# arduino-doorbell.net
KiCad netlist of a schematic drawn in EAGLE
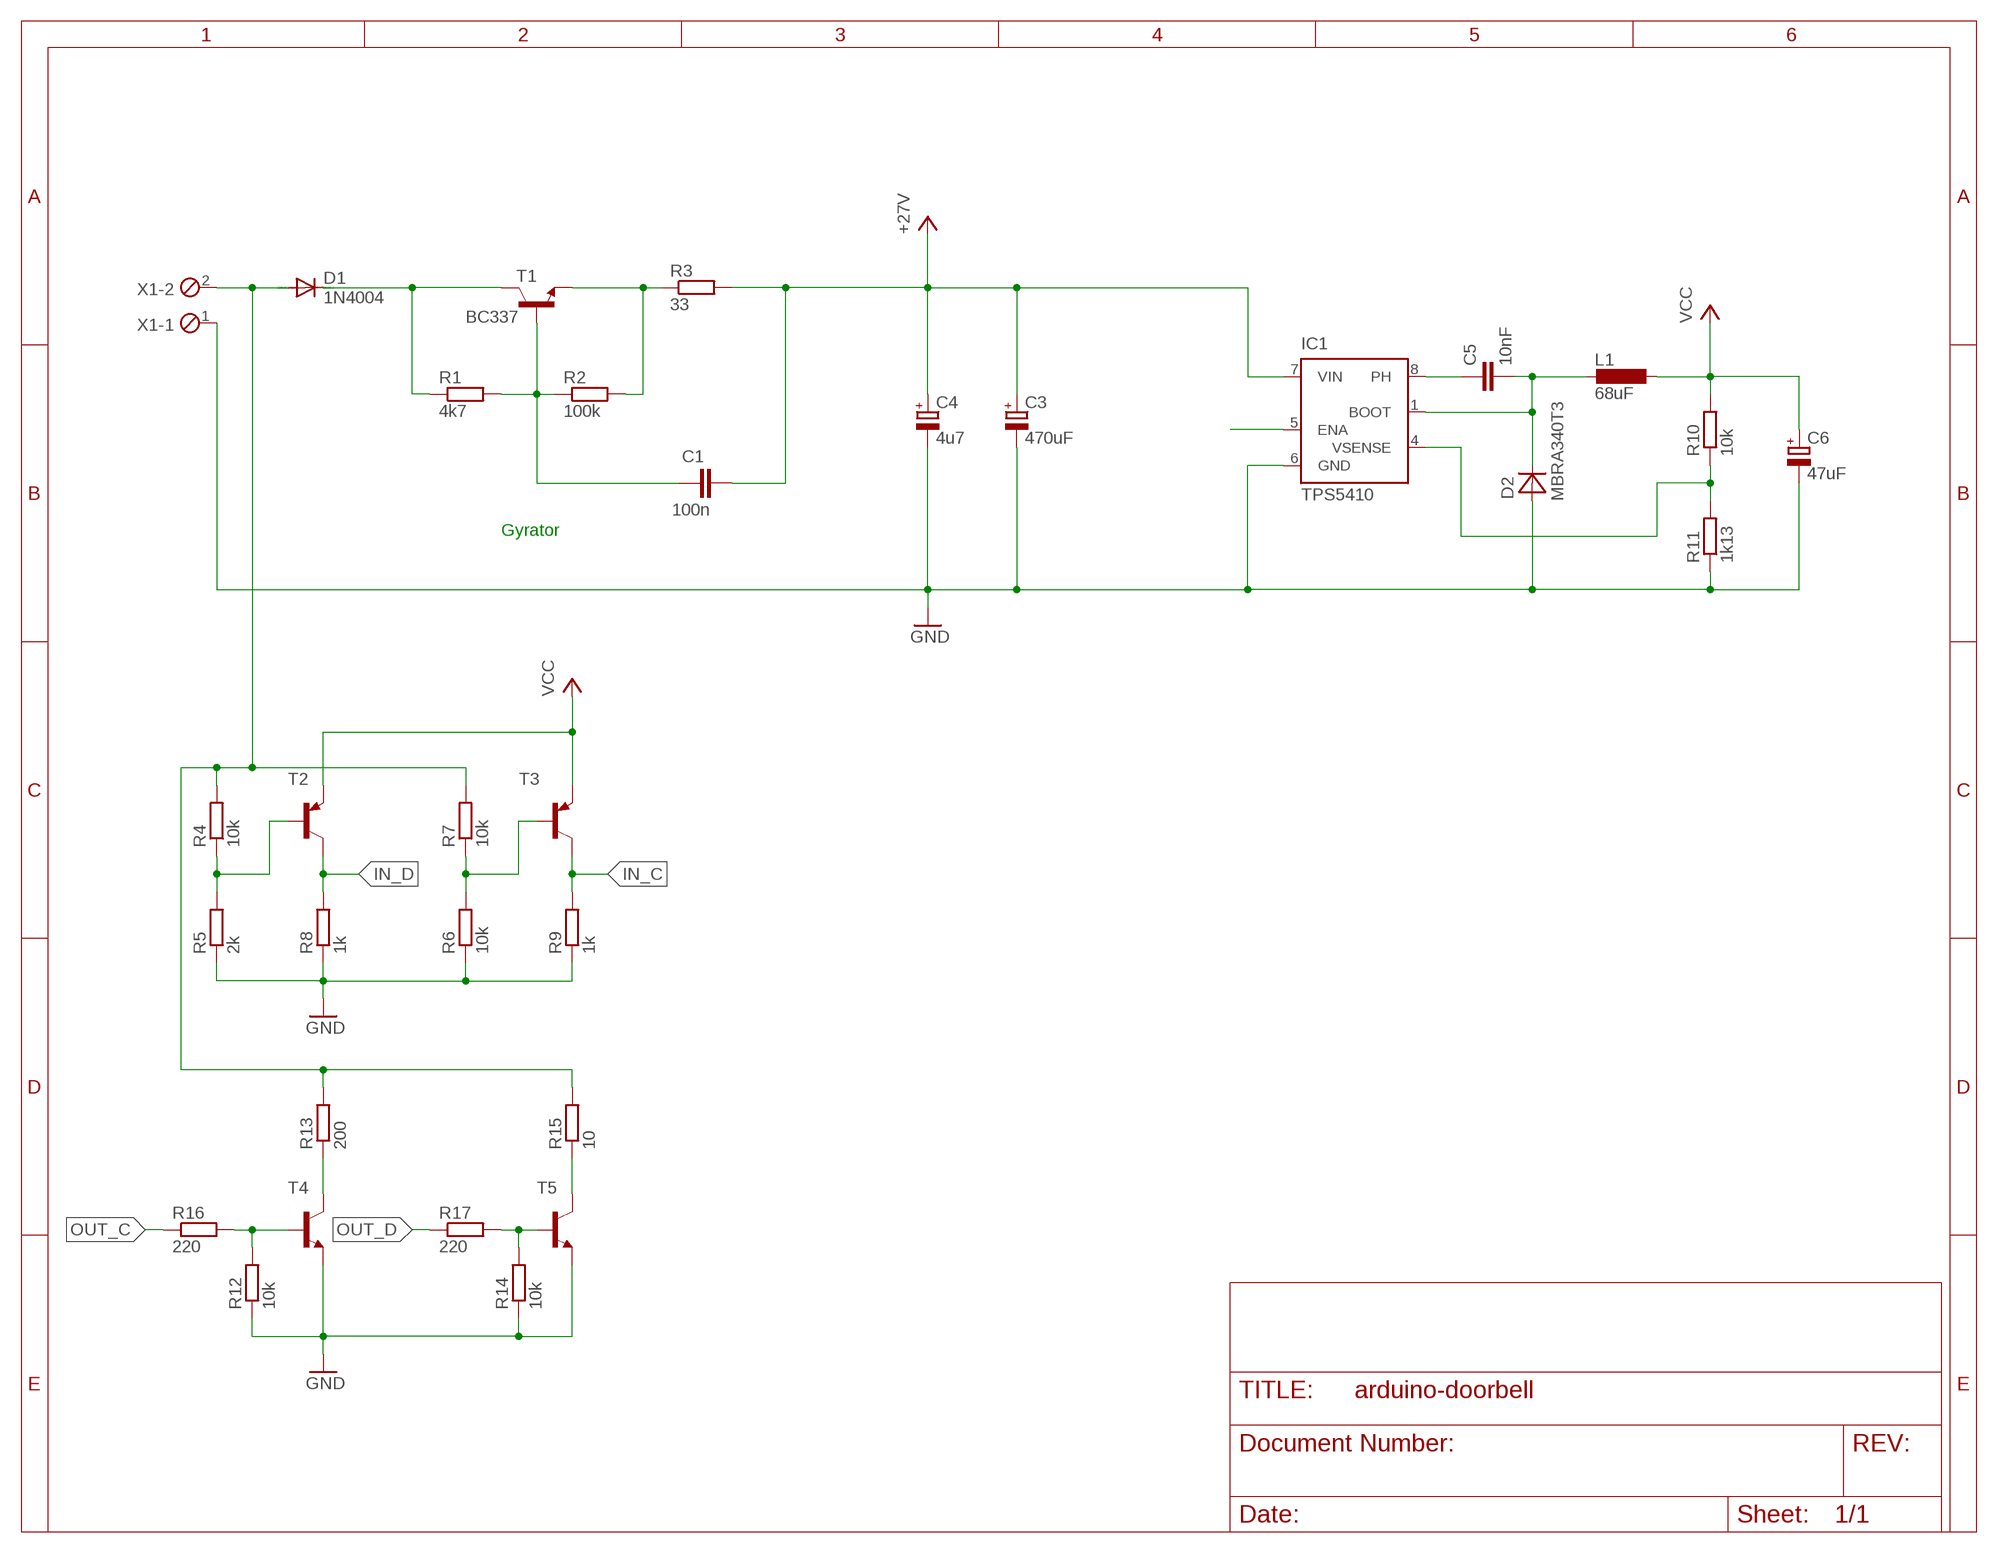
[diagram p0: schematic, sheet 1]

(export (version "E")
  (design (tool "Eeschema 10.0.6"))
  (components
    (comp (ref "C1")
      (value "100n")
      (footprint "eagle-import:C050-025X075")
      (libsource (lib "eagle-import") (part "C-EU050-025X075"))
    )
    (comp (ref "C3")
      (value "470uF")
      (footprint "eagle-import:E3,5-10")
      (libsource (lib "eagle-import") (part "CPOL-EUE3.5-10"))
    )
    (comp (ref "C4")
      (value "4u7")
      (footprint "eagle-import:E3,5-10")
      (libsource (lib "eagle-import") (part "CPOL-EUE3.5-10"))
    )
    (comp (ref "C5")
      (value "10nF")
      (footprint "eagle-import:C025-030X050")
      (libsource (lib "eagle-import") (part "C-EU025-030X050"))
    )
    (comp (ref "C6")
      (value "47uF")
      (footprint "eagle-import:E3,5-10")
      (libsource (lib "eagle-import") (part "CPOL-EUE3.5-10"))
    )
    (comp (ref "D1")
      (value "1N4004")
      (footprint "eagle-import:DO41-10")
      (libsource (lib "eagle-import") (part "1N4004"))
    )
    (comp (ref "D2")
      (value "MBRA340T3")
      (footprint "eagle-import:SMA")
      (libsource (lib "eagle-import") (part "MBRA340T3"))
    )
    (comp (ref "IC1")
      (value "TPS5410")
      (footprint "eagle-import:D_R-PDSO-G08")
      (fields (field (name "MPN") "TPS5410DR"))
      (libsource (lib "eagle-import") (part "TPS5410"))
    )
    (comp (ref "L1")
      (value "68uF")
      (footprint "eagle-import:DO3316P")
      (fields (field (name "MF") "MSS1260-683MLD"))
      (libsource (lib "eagle-import") (part "DO3316P"))
    )
    (comp (ref "R1")
      (value "4k7")
      (footprint "eagle-import:0204_5")
      (libsource (lib "eagle-import") (part "R-EU_0204/5"))
    )
    (comp (ref "R2")
      (value "100k")
      (footprint "eagle-import:0204_5")
      (libsource (lib "eagle-import") (part "R-EU_0204/5"))
    )
    (comp (ref "R3")
      (value "33")
      (footprint "eagle-import:0204_5")
      (libsource (lib "eagle-import") (part "R-EU_0204/5"))
    )
    (comp (ref "R4")
      (value "10k")
      (footprint "eagle-import:0204_5")
      (libsource (lib "eagle-import") (part "R-EU_0204/5"))
    )
    (comp (ref "R5")
      (value "2k")
      (footprint "eagle-import:0204_5")
      (libsource (lib "eagle-import") (part "R-EU_0204/5"))
    )
    (comp (ref "R6")
      (value "10k")
      (footprint "eagle-import:0204_5")
      (libsource (lib "eagle-import") (part "R-EU_0204/5"))
    )
    (comp (ref "R7")
      (value "10k")
      (footprint "eagle-import:0204_5")
      (libsource (lib "eagle-import") (part "R-EU_0204/5"))
    )
    (comp (ref "R8")
      (value "1k")
      (footprint "eagle-import:0204_5")
      (libsource (lib "eagle-import") (part "R-EU_0204/5"))
    )
    (comp (ref "R9")
      (value "1k")
      (footprint "eagle-import:0204_5")
      (libsource (lib "eagle-import") (part "R-EU_0204/5"))
    )
    (comp (ref "R10")
      (value "10k")
      (footprint "eagle-import:0204_5")
      (libsource (lib "eagle-import") (part "R-EU_0204/5"))
    )
    (comp (ref "R11")
      (value "1k13")
      (footprint "eagle-import:0204_5")
      (libsource (lib "eagle-import") (part "R-EU_0204/5"))
    )
    (comp (ref "R12")
      (value "10k")
      (footprint "eagle-import:0204_5")
      (libsource (lib "eagle-import") (part "R-EU_0204/5"))
    )
    (comp (ref "R13")
      (value "200")
      (footprint "eagle-import:0204_5")
      (libsource (lib "eagle-import") (part "R-EU_0204/5"))
    )
    (comp (ref "R14")
      (value "10k")
      (footprint "eagle-import:0204_5")
      (libsource (lib "eagle-import") (part "R-EU_0204/5"))
    )
    (comp (ref "R15")
      (value "10")
      (footprint "eagle-import:0204_5")
      (libsource (lib "eagle-import") (part "R-EU_0204/5"))
    )
    (comp (ref "R16")
      (value "220")
      (footprint "eagle-import:0204_5")
      (libsource (lib "eagle-import") (part "R-EU_0204/5"))
    )
    (comp (ref "R17")
      (value "220")
      (footprint "eagle-import:0204_5")
      (libsource (lib "eagle-import") (part "R-EU_0204/5"))
    )
    (comp (ref "T1")
      (value "BC337")
      (footprint "eagle-import:TO92")
      (libsource (lib "eagle-import") (part "BC337"))
    )
    (comp (ref "T2")
      (value "-PNP-TO92")
      (footprint "eagle-import:TO92")
      (libsource (lib "eagle-import") (part "-PNP-TO92"))
    )
    (comp (ref "T3")
      (value "-PNP-TO92")
      (footprint "eagle-import:TO92")
      (libsource (lib "eagle-import") (part "-PNP-TO92"))
    )
    (comp (ref "T4")
      (value "-NPN-SOT23-EBC")
      (footprint "eagle-import:SOT23-EBC")
      (libsource (lib "eagle-import") (part "-NPN-SOT23-EBC"))
    )
    (comp (ref "T5")
      (value "-NPN-SOT23-EBC")
      (footprint "eagle-import:SOT23-EBC")
      (libsource (lib "eagle-import") (part "-NPN-SOT23-EBC"))
    )
    (comp (ref "X1")
      (value "MPT2")
      (footprint "eagle-import:2POL254")
      (libsource (lib "eagle-import") (part "MPT2"))
    )
  )
  (nets
    (net (code "1") (name "+27V") (class "Default")
      (node (ref "C1") (pin "2") (pinfunction "2_2") (pintype "passive"))
      (node (ref "C3") (pin "+") (pinfunction "+_+") (pintype "passive"))
      (node (ref "C4") (pin "+") (pinfunction "+_+") (pintype "passive"))
      (node (ref "IC1") (pin "7") (pinfunction "VIN_7") (pintype "input"))
      (node (ref "R3") (pin "2") (pinfunction "2_2") (pintype "passive"))
    )
    (net (code "2") (name "GND") (class "Default")
      (node (ref "C3") (pin "-") (pinfunction "-_-") (pintype "passive"))
      (node (ref "C4") (pin "-") (pinfunction "-_-") (pintype "passive"))
      (node (ref "C6") (pin "-") (pinfunction "-_-") (pintype "passive"))
      (node (ref "D2") (pin "A") (pinfunction "A_A") (pintype "passive"))
      (node (ref "IC1") (pin "6") (pinfunction "GND_6") (pintype "power_in"))
      (node (ref "R11") (pin "1") (pinfunction "1_1") (pintype "passive"))
      (node (ref "R12") (pin "1") (pinfunction "1_1") (pintype "passive"))
      (node (ref "R14") (pin "1") (pinfunction "1_1") (pintype "passive"))
      (node (ref "R5") (pin "1") (pinfunction "1_1") (pintype "passive"))
      (node (ref "R6") (pin "1") (pinfunction "1_1") (pintype "passive"))
      (node (ref "R8") (pin "1") (pinfunction "1_1") (pintype "passive"))
      (node (ref "R9") (pin "1") (pinfunction "1_1") (pintype "passive"))
      (node (ref "T4") (pin "E") (pinfunction "E_E") (pintype "passive"))
      (node (ref "T5") (pin "E") (pinfunction "E_E") (pintype "passive"))
      (node (ref "X1") (pin "1") (pinfunction "1_1") (pintype "passive"))
    )
    (net (code "3") (name "IN_C") (class "Default")
      (node (ref "R9") (pin "2") (pinfunction "2_2") (pintype "passive"))
      (node (ref "T3") (pin "3") (pinfunction "C_3") (pintype "passive"))
    )
    (net (code "4") (name "IN_D") (class "Default")
      (node (ref "R8") (pin "2") (pinfunction "2_2") (pintype "passive"))
      (node (ref "T2") (pin "3") (pinfunction "C_3") (pintype "passive"))
    )
    (net (code "5") (name "Net-(IC1-BOOT)") (class "Default")
      (node (ref "C5") (pin "2") (pinfunction "2_2") (pintype "passive"))
      (node (ref "D2") (pin "C") (pinfunction "C_C") (pintype "passive"))
      (node (ref "IC1") (pin "1") (pinfunction "BOOT_1") (pintype "output"))
      (node (ref "L1") (pin "1") (pinfunction "1_1") (pintype "passive"))
    )
    (net (code "6") (name "Net-(IC1-PH)") (class "Default")
      (node (ref "C5") (pin "1") (pinfunction "1_1") (pintype "passive"))
      (node (ref "IC1") (pin "8") (pinfunction "PH_8") (pintype "output"))
    )
    (net (code "7") (name "Net-(IC1-VSENSE)") (class "Default")
      (node (ref "IC1") (pin "4") (pinfunction "VSENSE_4") (pintype "input"))
      (node (ref "R10") (pin "1") (pinfunction "1_1") (pintype "passive"))
      (node (ref "R11") (pin "2") (pinfunction "2_2") (pintype "passive"))
    )
    (net (code "8") (name "Net-(R12-Pad2)") (class "Default")
      (node (ref "R12") (pin "2") (pinfunction "2_2") (pintype "passive"))
      (node (ref "R16") (pin "2") (pinfunction "2_2") (pintype "passive"))
      (node (ref "T4") (pin "B") (pinfunction "B_B") (pintype "passive"))
    )
    (net (code "9") (name "Net-(R13-Pad1)") (class "Default")
      (node (ref "R13") (pin "1") (pinfunction "1_1") (pintype "passive"))
      (node (ref "T4") (pin "C") (pinfunction "C_C") (pintype "passive"))
    )
    (net (code "10") (name "Net-(R14-Pad2)") (class "Default")
      (node (ref "R14") (pin "2") (pinfunction "2_2") (pintype "passive"))
      (node (ref "R17") (pin "2") (pinfunction "2_2") (pintype "passive"))
      (node (ref "T5") (pin "B") (pinfunction "B_B") (pintype "passive"))
    )
    (net (code "11") (name "Net-(R15-Pad1)") (class "Default")
      (node (ref "R15") (pin "1") (pinfunction "1_1") (pintype "passive"))
      (node (ref "T5") (pin "C") (pinfunction "C_C") (pintype "passive"))
    )
    (net (code "12") (name "Net-(T1-B)") (class "Default")
      (node (ref "C1") (pin "1") (pinfunction "1_1") (pintype "passive"))
      (node (ref "R1") (pin "2") (pinfunction "2_2") (pintype "passive"))
      (node (ref "R2") (pin "1") (pinfunction "1_1") (pintype "passive"))
      (node (ref "T1") (pin "2") (pinfunction "B_2") (pintype "passive"))
    )
    (net (code "13") (name "Net-(T1-C)") (class "Default")
      (node (ref "D1") (pin "C") (pinfunction "C_C") (pintype "passive"))
      (node (ref "R1") (pin "1") (pinfunction "1_1") (pintype "passive"))
      (node (ref "T1") (pin "3") (pinfunction "C_3") (pintype "passive"))
    )
    (net (code "14") (name "Net-(T1-E)") (class "Default")
      (node (ref "R2") (pin "2") (pinfunction "2_2") (pintype "passive"))
      (node (ref "R3") (pin "1") (pinfunction "1_1") (pintype "passive"))
      (node (ref "T1") (pin "1") (pinfunction "E_1") (pintype "passive"))
    )
    (net (code "15") (name "Net-(T2-B)") (class "Default")
      (node (ref "R4") (pin "1") (pinfunction "1_1") (pintype "passive"))
      (node (ref "R5") (pin "2") (pinfunction "2_2") (pintype "passive"))
      (node (ref "T2") (pin "2") (pinfunction "B_2") (pintype "passive"))
    )
    (net (code "16") (name "Net-(T3-B)") (class "Default")
      (node (ref "R6") (pin "2") (pinfunction "2_2") (pintype "passive"))
      (node (ref "R7") (pin "1") (pinfunction "1_1") (pintype "passive"))
      (node (ref "T3") (pin "2") (pinfunction "B_2") (pintype "passive"))
    )
    (net (code "17") (name "Net-(X1B-1)") (class "Default")
      (node (ref "D1") (pin "A") (pinfunction "A_A") (pintype "passive"))
      (node (ref "R13") (pin "2") (pinfunction "2_2") (pintype "passive"))
      (node (ref "R15") (pin "2") (pinfunction "2_2") (pintype "passive"))
      (node (ref "R4") (pin "2") (pinfunction "2_2") (pintype "passive"))
      (node (ref "R7") (pin "2") (pinfunction "2_2") (pintype "passive"))
      (node (ref "X1") (pin "2") (pinfunction "1_2") (pintype "passive"))
    )
    (net (code "18") (name "OUT_C") (class "Default")
      (node (ref "R16") (pin "1") (pinfunction "1_1") (pintype "passive"))
    )
    (net (code "19") (name "OUT_D") (class "Default")
      (node (ref "R17") (pin "1") (pinfunction "1_1") (pintype "passive"))
    )
    (net (code "20") (name "VCC") (class "Default")
      (node (ref "C6") (pin "+") (pinfunction "+_+") (pintype "passive"))
      (node (ref "L1") (pin "2") (pinfunction "2_2") (pintype "passive"))
      (node (ref "R10") (pin "2") (pinfunction "2_2") (pintype "passive"))
      (node (ref "T2") (pin "1") (pinfunction "E_1") (pintype "passive"))
      (node (ref "T3") (pin "1") (pinfunction "E_1") (pintype "passive"))
    )
    (net (code "21") (name "unconnected-(IC1-ENA-Pad5)") (class "Default")
      (node (ref "IC1") (pin "5") (pinfunction "ENA_5") (pintype "input"))
    )
  )
)
